# MCU.net
KiCad netlist of a schematic drawn in Altium Designer
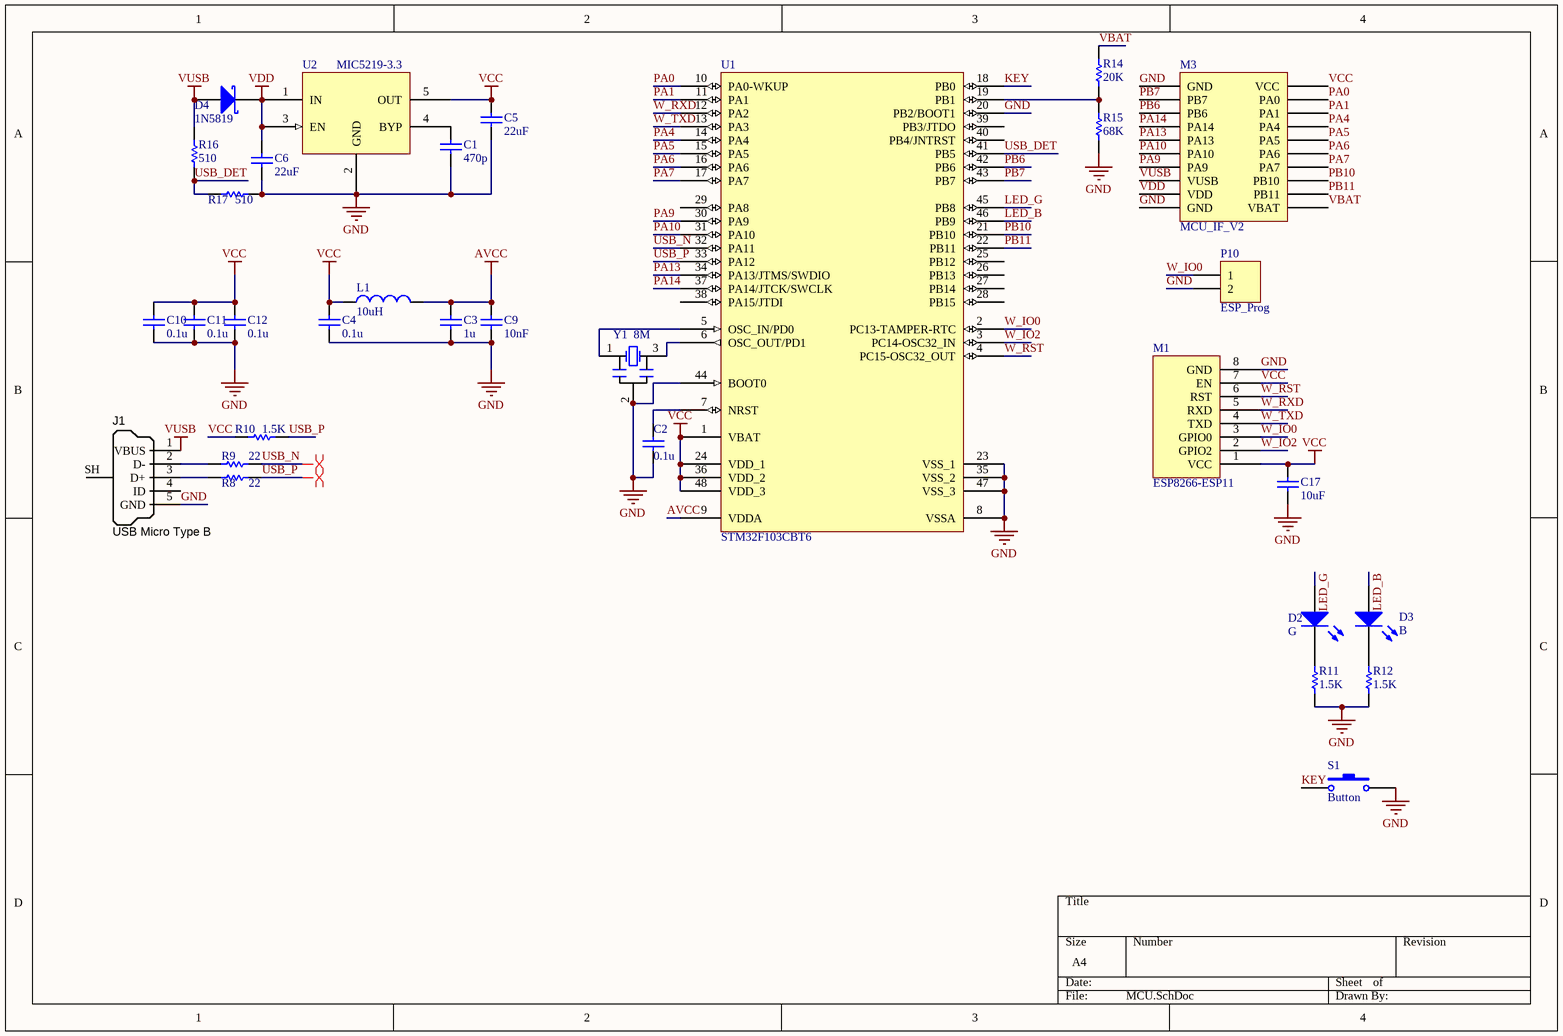
[diagram p0: MCU.SchDoc]

(export (version "E")
  (design (tool "Eeschema 10.0.6"))
  (components
    (comp (ref "C1")
      (value "470p")
      (footprint "C-1608[0603]")
      (description "Capacitor (Semiconductor SIM Model)")
      (fields (field (name "Comment") "Cap Semi") (field (name "PUBLISHER") "Altium Limited"))
      (libsource (lib "Miscellaneous Devices") (part "Cap Semi"))
    )
    (comp (ref "C2")
      (value "0.1u")
      (footprint "C-1608[0603]")
      (description "Capacitor (Semiconductor SIM Model)")
      (fields (field (name "Comment") "Cap Semi") (field (name "PUBLISHER") "Altium Limited"))
      (libsource (lib "Miscellaneous Devices") (part "Cap Semi"))
    )
    (comp (ref "C3")
      (value "1u")
      (footprint "C-1608[0603]")
      (description "Capacitor (Semiconductor SIM Model)")
      (fields (field (name "Comment") "Cap Semi") (field (name "PUBLISHER") "Altium Limited"))
      (libsource (lib "Miscellaneous Devices") (part "Cap Semi"))
    )
    (comp (ref "C4")
      (value "0.1u")
      (footprint "C-1608[0603]")
      (description "Capacitor (Semiconductor SIM Model)")
      (fields (field (name "Comment") "Cap Semi") (field (name "PUBLISHER") "Altium Limited"))
      (libsource (lib "Miscellaneous Devices") (part "Cap Semi"))
    )
    (comp (ref "C5")
      (value "22uF")
      (footprint "C-2012[0805]")
      (description "Capacitor (Semiconductor SIM Model)")
      (fields (field (name "Comment") "Cap Semi") (field (name "PUBLISHER") "Altium Limited"))
      (libsource (lib "Miscellaneous Devices") (part "Cap Semi"))
    )
    (comp (ref "C6")
      (value "22uF")
      (footprint "C-2012[0805]")
      (description "Capacitor (Semiconductor SIM Model)")
      (fields (field (name "Comment") "Cap Semi") (field (name "PUBLISHER") "Altium Limited"))
      (libsource (lib "Miscellaneous Devices") (part "Cap Semi"))
    )
    (comp (ref "C9")
      (value "10nF")
      (footprint "C-1608[0603]")
      (description "Capacitor (Semiconductor SIM Model)")
      (fields (field (name "Comment") "Cap Semi") (field (name "PUBLISHER") "Altium Limited"))
      (libsource (lib "Miscellaneous Devices") (part "Cap Semi"))
    )
    (comp (ref "C10")
      (value "0.1u")
      (footprint "C-1608[0603]")
      (description "Capacitor (Semiconductor SIM Model)")
      (fields (field (name "Comment") "Cap Semi") (field (name "PUBLISHER") "Altium Limited"))
      (libsource (lib "Miscellaneous Devices") (part "Cap Semi"))
    )
    (comp (ref "C11")
      (value "0.1u")
      (footprint "C-1608[0603]")
      (description "Capacitor (Semiconductor SIM Model)")
      (fields (field (name "Comment") "Cap Semi") (field (name "PUBLISHER") "Altium Limited"))
      (libsource (lib "Miscellaneous Devices") (part "Cap Semi"))
    )
    (comp (ref "C12")
      (value "0.1u")
      (footprint "C-1608[0603]")
      (description "Capacitor (Semiconductor SIM Model)")
      (fields (field (name "Comment") "Cap Semi") (field (name "PUBLISHER") "Altium Limited"))
      (libsource (lib "Miscellaneous Devices") (part "Cap Semi"))
    )
    (comp (ref "C17")
      (value "10uF")
      (footprint "C-1608[0603]")
      (description "Capacitor (Semiconductor SIM Model)")
      (fields (field (name "Comment") "Cap Semi") (field (name "PUBLISHER") "Altium Limited"))
      (libsource (lib "Miscellaneous Devices") (part "Cap Semi"))
    )
    (comp (ref "D2")
      (value "G")
      (footprint "LED-1608[0603]-G")
      (description "Green LED")
      (fields (field (name "PUBLISHER") "Altium Limited"))
      (libsource (lib "Miscellaneous Devices") (part "LED2"))
    )
    (comp (ref "D3")
      (value "B")
      (footprint "LED-1608[0603]-B")
      (description "Blue LED")
      (fields (field (name "PUBLISHER") "Altium Limited"))
      (libsource (lib "Miscellaneous Devices") (part "LED2"))
    )
    (comp (ref "D4")
      (value "1N5819")
      (footprint "PcbLib1:SOD123")
      (description "Schottky Diode")
      (fields (field (name "PUBLISHER") "Altium Limited"))
      (libsource (lib "Miscellaneous Devices") (part "D Schottky"))
    )
    (comp (ref "J1")
      (value "USB Micro Type B")
      (footprint "MICRO USB 3D")
      (description "Connector SMD USB Micro Type B middle mount")
      (libsource (lib "Schlib1") (part "USB_Micro_TypeB"))
    )
    (comp (ref "L1")
      (value "10uH")
      (footprint "L-1608[0603]")
      (description "Inductor")
      (fields (field (name "PUBLISHER") "Altium Limited"))
      (libsource (lib "Miscellaneous Devices") (part "Inductor"))
    )
    (comp (ref "M1")
      (value "ESP8266-ESP11")
      (footprint "ESP8266-ESP11")
      (libsource (lib "WiFiMod") (part "ESP8266-ESP11"))
    )
    (comp (ref "M3")
      (value "MCU_IF_V2")
      (footprint "MCU_IF_V2")
      (libsource (lib "MCU_IF") (part "MCU_IF_V1"))
    )
    (comp (ref "P10")
      (value "ESP_Prog")
      (footprint "EDGE_1")
      (description "Header, 2-Pin")
      (fields (field (name "PUBLISHER") "Altium Limited"))
      (libsource (lib "Miscellaneous Connectors") (part "Header 2"))
    )
    (comp (ref "R8")
      (value "22")
      (footprint "R-1608[0603]")
      (description "Semiconductor Resistor")
      (fields (field (name "Comment") "Res Semi") (field (name "PUBLISHER") "Altium Limited"))
      (libsource (lib "Miscellaneous Devices") (part "Res Semi"))
    )
    (comp (ref "R9")
      (value "22")
      (footprint "R-1608[0603]")
      (description "Semiconductor Resistor")
      (fields (field (name "Comment") "Res Semi") (field (name "PUBLISHER") "Altium Limited"))
      (libsource (lib "Miscellaneous Devices") (part "Res Semi"))
    )
    (comp (ref "R10")
      (value "1.5K")
      (footprint "R-1608[0603]")
      (description "Semiconductor Resistor")
      (fields (field (name "Comment") "Res Semi") (field (name "PUBLISHER") "Altium Limited"))
      (libsource (lib "Miscellaneous Devices") (part "Res Semi"))
    )
    (comp (ref "R11")
      (value "1.5K")
      (footprint "R-1608[0603]")
      (description "Semiconductor Resistor")
      (fields (field (name "Comment") "Res Semi") (field (name "PUBLISHER") "Altium Limited"))
      (libsource (lib "Miscellaneous Devices") (part "Res Semi"))
    )
    (comp (ref "R12")
      (value "1.5K")
      (footprint "R-1608[0603]")
      (description "Semiconductor Resistor")
      (fields (field (name "Comment") "Res Semi") (field (name "PUBLISHER") "Altium Limited"))
      (libsource (lib "Miscellaneous Devices") (part "Res Semi"))
    )
    (comp (ref "R14")
      (value "20K")
      (footprint "R-1608[0603]")
      (description "Semiconductor Resistor")
      (fields (field (name "Comment") "Res Semi") (field (name "PUBLISHER") "Altium Limited"))
      (libsource (lib "Miscellaneous Devices") (part "Res Semi"))
    )
    (comp (ref "R15")
      (value "68K")
      (footprint "R-1608[0603]")
      (description "Semiconductor Resistor")
      (fields (field (name "Comment") "Res Semi") (field (name "PUBLISHER") "Altium Limited"))
      (libsource (lib "Miscellaneous Devices") (part "Res Semi"))
    )
    (comp (ref "R16")
      (value "510")
      (footprint "R-1608[0603]")
      (description "Semiconductor Resistor")
      (fields (field (name "Comment") "Res Semi") (field (name "PUBLISHER") "Altium Limited"))
      (libsource (lib "Miscellaneous Devices") (part "Res Semi"))
    )
    (comp (ref "R17")
      (value "510")
      (footprint "R-1608[0603]")
      (description "Semiconductor Resistor")
      (fields (field (name "Comment") "Res Semi") (field (name "PUBLISHER") "Altium Limited"))
      (libsource (lib "Miscellaneous Devices") (part "Res Semi"))
    )
    (comp (ref "S1")
      (value "Button")
      (footprint "SW-2pin-SMD")
      (description "Switch")
      (fields (field (name "PUBLISHER") "Altium Limited"))
      (libsource (lib "Miscellaneous Devices") (part "SW-PB"))
    )
    (comp (ref "U1")
      (value "STM32F103CBT6")
      (footprint "LQFP48_N")
      (description "STM32 ARM-based 32-bit MCU with 128 Kbytes Flash, 48-pin LQFP, Industrial Temperature")
      (fields (field (name "PUBLISHER") "Altium Limited"))
      (libsource (lib "ST Microcontroller 32-Bit STM32") (part "STM32F103CBT6"))
    )
    (comp (ref "U2")
      (value "MIC5219-3.3")
      (footprint "SOT23-5")
      (description "500mA-Peak Output LDO Regulator")
      (libsource (lib "Schlib1") (part "MIC5219"))
    )
    (comp (ref "Y1")
      (value "8M")
      (footprint "Crystal_C")
      (description "Crystal Oscillator")
      (fields (field (name "PUBLISHER") "Altium Limited"))
      (libsource (lib "Schlib1") (part "XTAL_C"))
    )
  )
  (nets
    (net (code "1") (name "/KEY") (class "Default")
      (node (ref "S1") (pin "1") (pinfunction "1_1") (pintype "passive"))
      (node (ref "U1") (pin "18") (pinfunction "PB0_18") (pintype "bidirectional"))
    )
    (net (code "2") (name "/LED_B") (class "Default")
      (node (ref "D3") (pin "1") (pinfunction "A_1") (pintype "passive"))
      (node (ref "U1") (pin "46") (pinfunction "PB9_46") (pintype "bidirectional"))
    )
    (net (code "3") (name "/LED_G") (class "Default")
      (node (ref "D2") (pin "1") (pinfunction "A_1") (pintype "passive"))
      (node (ref "U1") (pin "45") (pinfunction "PB8_45") (pintype "bidirectional"))
    )
    (net (code "4") (name "/PA0") (class "Default")
      (node (ref "M3") (pin "19") (pinfunction "PA0_19") (pintype "passive"))
      (node (ref "U1") (pin "10") (pinfunction "PA0-WKUP_10") (pintype "bidirectional"))
    )
    (net (code "5") (name "/PA1") (class "Default")
      (node (ref "M3") (pin "18") (pinfunction "PA1_18") (pintype "passive"))
      (node (ref "U1") (pin "11") (pinfunction "PA1_11") (pintype "bidirectional"))
    )
    (net (code "6") (name "/PA4") (class "Default")
      (node (ref "M3") (pin "17") (pinfunction "PA4_17") (pintype "passive"))
      (node (ref "U1") (pin "14") (pinfunction "PA4_14") (pintype "bidirectional"))
    )
    (net (code "7") (name "/PA5") (class "Default")
      (node (ref "M3") (pin "16") (pinfunction "PA5_16") (pintype "passive"))
      (node (ref "U1") (pin "15") (pinfunction "PA5_15") (pintype "bidirectional"))
    )
    (net (code "8") (name "/PA6") (class "Default")
      (node (ref "M3") (pin "15") (pinfunction "PA6_15") (pintype "passive"))
      (node (ref "U1") (pin "16") (pinfunction "PA6_16") (pintype "bidirectional"))
    )
    (net (code "9") (name "/PA7") (class "Default")
      (node (ref "M3") (pin "14") (pinfunction "PA7_14") (pintype "passive"))
      (node (ref "U1") (pin "17") (pinfunction "PA7_17") (pintype "bidirectional"))
    )
    (net (code "10") (name "/PA9") (class "Default")
      (node (ref "M3") (pin "7") (pinfunction "PA9_7") (pintype "passive"))
      (node (ref "U1") (pin "30") (pinfunction "PA9_30") (pintype "bidirectional"))
    )
    (net (code "11") (name "/PA10") (class "Default")
      (node (ref "M3") (pin "6") (pinfunction "PA10_6") (pintype "passive"))
      (node (ref "U1") (pin "31") (pinfunction "PA10_31") (pintype "bidirectional"))
    )
    (net (code "12") (name "/PA13") (class "Default")
      (node (ref "M3") (pin "5") (pinfunction "PA13_5") (pintype "passive"))
      (node (ref "U1") (pin "34") (pinfunction "PA13/JTMS/SWDIO_34") (pintype "bidirectional"))
    )
    (net (code "13") (name "/PA14") (class "Default")
      (node (ref "M3") (pin "4") (pinfunction "PA14_4") (pintype "passive"))
      (node (ref "U1") (pin "37") (pinfunction "PA14/JTCK/SWCLK_37") (pintype "bidirectional"))
    )
    (net (code "14") (name "/PB6") (class "Default")
      (node (ref "M3") (pin "3") (pinfunction "PB6_3") (pintype "passive"))
      (node (ref "U1") (pin "42") (pinfunction "PB6_42") (pintype "bidirectional"))
    )
    (net (code "15") (name "/PB7") (class "Default")
      (node (ref "M3") (pin "2") (pinfunction "PB7_2") (pintype "passive"))
      (node (ref "U1") (pin "43") (pinfunction "PB7_43") (pintype "bidirectional"))
    )
    (net (code "16") (name "/PB10") (class "Default")
      (node (ref "M3") (pin "13") (pinfunction "PB10_13") (pintype "passive"))
      (node (ref "U1") (pin "21") (pinfunction "PB10_21") (pintype "bidirectional"))
    )
    (net (code "17") (name "/PB11") (class "Default")
      (node (ref "M3") (pin "12") (pinfunction "PB11_12") (pintype "passive"))
      (node (ref "U1") (pin "22") (pinfunction "PB11_22") (pintype "bidirectional"))
    )
    (net (code "18") (name "/USB_DET") (class "Default")
      (node (ref "R16") (pin "1") (pinfunction "1_1") (pintype "passive"))
      (node (ref "R17") (pin "2") (pinfunction "2_2") (pintype "passive"))
      (node (ref "U1") (pin "41") (pinfunction "PB5_41") (pintype "bidirectional"))
    )
    (net (code "19") (name "/USB_N") (class "Default")
      (node (ref "R9") (pin "2") (pinfunction "2_2") (pintype "passive"))
      (node (ref "U1") (pin "32") (pinfunction "PA11_32") (pintype "bidirectional"))
    )
    (net (code "20") (name "/USB_P") (class "Default")
      (node (ref "R10") (pin "1") (pinfunction "1_1") (pintype "passive"))
      (node (ref "R8") (pin "2") (pinfunction "2_2") (pintype "passive"))
      (node (ref "U1") (pin "33") (pinfunction "PA12_33") (pintype "bidirectional"))
    )
    (net (code "21") (name "/VBAT") (class "Default")
      (node (ref "M3") (pin "11") (pinfunction "VBAT_11") (pintype "passive"))
      (node (ref "R14") (pin "2") (pinfunction "2_2") (pintype "passive"))
    )
    (net (code "22") (name "/W_IO0") (class "Default")
      (node (ref "M1") (pin "3") (pinfunction "GPIO0_3") (pintype "passive"))
      (node (ref "P10") (pin "1") (pinfunction "1_1") (pintype "passive"))
      (node (ref "U1") (pin "2") (pinfunction "PC13-TAMPER-RTC_2") (pintype "bidirectional"))
    )
    (net (code "23") (name "/W_IO2") (class "Default")
      (node (ref "M1") (pin "2") (pinfunction "GPIO2_2") (pintype "passive"))
      (node (ref "U1") (pin "3") (pinfunction "PC14-OSC32_IN_3") (pintype "bidirectional"))
    )
    (net (code "24") (name "/W_RST") (class "Default")
      (node (ref "M1") (pin "6") (pinfunction "RST_6") (pintype "passive"))
      (node (ref "U1") (pin "4") (pinfunction "PC15-OSC32_OUT_4") (pintype "bidirectional"))
    )
    (net (code "25") (name "/W_RXD") (class "Default")
      (node (ref "M1") (pin "5") (pinfunction "RXD_5") (pintype "passive"))
      (node (ref "U1") (pin "12") (pinfunction "PA2_12") (pintype "bidirectional"))
    )
    (net (code "26") (name "/W_TXD") (class "Default")
      (node (ref "M1") (pin "4") (pinfunction "TXD_4") (pintype "passive"))
      (node (ref "U1") (pin "13") (pinfunction "PA3_13") (pintype "bidirectional"))
    )
    (net (code "27") (name "AVCC") (class "Default")
      (node (ref "C3") (pin "2") (pinfunction "2_2") (pintype "passive"))
      (node (ref "C9") (pin "2") (pinfunction "2_2") (pintype "passive"))
      (node (ref "L1") (pin "2") (pinfunction "2_2") (pintype "passive"))
      (node (ref "U1") (pin "9") (pinfunction "VDDA_9") (pintype "power_in"))
    )
    (net (code "28") (name "GND") (class "Default")
      (node (ref "C1") (pin "2") (pinfunction "2_2") (pintype "passive"))
      (node (ref "C10") (pin "1") (pinfunction "1_1") (pintype "passive"))
      (node (ref "C11") (pin "1") (pinfunction "1_1") (pintype "passive"))
      (node (ref "C12") (pin "1") (pinfunction "1_1") (pintype "passive"))
      (node (ref "C17") (pin "1") (pinfunction "1_1") (pintype "passive"))
      (node (ref "C2") (pin "1") (pinfunction "1_1") (pintype "passive"))
      (node (ref "C3") (pin "1") (pinfunction "1_1") (pintype "passive"))
      (node (ref "C4") (pin "1") (pinfunction "1_1") (pintype "passive"))
      (node (ref "C5") (pin "2") (pinfunction "2_2") (pintype "passive"))
      (node (ref "C6") (pin "2") (pinfunction "2_2") (pintype "passive"))
      (node (ref "C9") (pin "1") (pinfunction "1_1") (pintype "passive"))
      (node (ref "J1") (pin "5") (pinfunction "GND_5") (pintype "passive"))
      (node (ref "M1") (pin "8") (pinfunction "GND_8") (pintype "passive"))
      (node (ref "M3") (pin "1") (pinfunction "GND_1") (pintype "passive"))
      (node (ref "M3") (pin "10") (pinfunction "GND_10") (pintype "passive"))
      (node (ref "P10") (pin "2") (pinfunction "2_2") (pintype "passive"))
      (node (ref "R11") (pin "2") (pinfunction "2_2") (pintype "passive"))
      (node (ref "R12") (pin "2") (pinfunction "2_2") (pintype "passive"))
      (node (ref "R15") (pin "2") (pinfunction "2_2") (pintype "passive"))
      (node (ref "R17") (pin "1") (pinfunction "1_1") (pintype "passive"))
      (node (ref "S1") (pin "2") (pinfunction "2_2") (pintype "passive"))
      (node (ref "U1") (pin "20") (pinfunction "PB2/BOOT1_20") (pintype "bidirectional"))
      (node (ref "U1") (pin "23") (pinfunction "VSS_1_23") (pintype "power_in"))
      (node (ref "U1") (pin "35") (pinfunction "VSS_2_35") (pintype "power_in"))
      (node (ref "U1") (pin "44") (pinfunction "BOOT0_44") (pintype "input"))
      (node (ref "U1") (pin "47") (pinfunction "VSS_3_47") (pintype "power_in"))
      (node (ref "U1") (pin "8") (pinfunction "VSSA_8") (pintype "power_in"))
      (node (ref "U2") (pin "2") (pinfunction "GND_2") (pintype "passive"))
      (node (ref "Y1") (pin "2") (pinfunction "GND_2") (pintype "passive"))
    )
    (net (code "29") (name "Net-(D2-K)") (class "Default")
      (node (ref "D2") (pin "2") (pinfunction "K_2") (pintype "passive"))
      (node (ref "R11") (pin "1") (pinfunction "1_1") (pintype "passive"))
    )
    (net (code "30") (name "Net-(D3-K)") (class "Default")
      (node (ref "D3") (pin "2") (pinfunction "K_2") (pintype "passive"))
      (node (ref "R12") (pin "1") (pinfunction "1_1") (pintype "passive"))
    )
    (net (code "31") (name "Net-(J1-D+)") (class "Default")
      (node (ref "J1") (pin "3") (pinfunction "D+_3") (pintype "passive"))
      (node (ref "R8") (pin "1") (pinfunction "1_1") (pintype "passive"))
    )
    (net (code "32") (name "Net-(J1-D-)") (class "Default")
      (node (ref "J1") (pin "2") (pinfunction "D-_2") (pintype "passive"))
      (node (ref "R9") (pin "1") (pinfunction "1_1") (pintype "passive"))
    )
    (net (code "33") (name "Net-(U1-NRST)") (class "Default")
      (node (ref "C2") (pin "2") (pinfunction "2_2") (pintype "passive"))
      (node (ref "U1") (pin "7") (pinfunction "NRST_7") (pintype "bidirectional"))
    )
    (net (code "34") (name "Net-(U1-OSC_IN{slash}PD0)") (class "Default")
      (node (ref "U1") (pin "5") (pinfunction "OSC_IN/PD0_5") (pintype "input"))
      (node (ref "Y1") (pin "1") (pinfunction "OSC1_1") (pintype "passive"))
    )
    (net (code "35") (name "Net-(U1-OSC_OUT{slash}PD1)") (class "Default")
      (node (ref "U1") (pin "6") (pinfunction "OSC_OUT/PD1_6") (pintype "output"))
      (node (ref "Y1") (pin "3") (pinfunction "OSC2_3") (pintype "passive"))
    )
    (net (code "36") (name "Net-(U1-PB1)") (class "Default")
      (node (ref "R14") (pin "1") (pinfunction "1_1") (pintype "passive"))
      (node (ref "R15") (pin "1") (pinfunction "1_1") (pintype "passive"))
      (node (ref "U1") (pin "19") (pinfunction "PB1_19") (pintype "bidirectional"))
    )
    (net (code "37") (name "Net-(U2-BYP)") (class "Default")
      (node (ref "C1") (pin "1") (pinfunction "1_1") (pintype "passive"))
      (node (ref "U2") (pin "4") (pinfunction "BYP_4") (pintype "passive"))
    )
    (net (code "38") (name "VCC") (class "Default")
      (node (ref "C10") (pin "2") (pinfunction "2_2") (pintype "passive"))
      (node (ref "C11") (pin "2") (pinfunction "2_2") (pintype "passive"))
      (node (ref "C12") (pin "2") (pinfunction "2_2") (pintype "passive"))
      (node (ref "C17") (pin "2") (pinfunction "2_2") (pintype "passive"))
      (node (ref "C4") (pin "2") (pinfunction "2_2") (pintype "passive"))
      (node (ref "C5") (pin "1") (pinfunction "1_1") (pintype "passive"))
      (node (ref "L1") (pin "1") (pinfunction "1_1") (pintype "passive"))
      (node (ref "M1") (pin "1") (pinfunction "VCC_1") (pintype "power_in"))
      (node (ref "M1") (pin "7") (pinfunction "EN_7") (pintype "passive"))
      (node (ref "M3") (pin "20") (pinfunction "VCC_20") (pintype "passive"))
      (node (ref "R10") (pin "2") (pinfunction "2_2") (pintype "passive"))
      (node (ref "U1") (pin "1") (pinfunction "VBAT_1") (pintype "power_in"))
      (node (ref "U1") (pin "24") (pinfunction "VDD_1_24") (pintype "power_in"))
      (node (ref "U1") (pin "36") (pinfunction "VDD_2_36") (pintype "power_in"))
      (node (ref "U1") (pin "48") (pinfunction "VDD_3_48") (pintype "power_in"))
      (node (ref "U2") (pin "5") (pinfunction "OUT_5") (pintype "passive"))
    )
    (net (code "39") (name "VDD") (class "Default")
      (node (ref "C6") (pin "1") (pinfunction "1_1") (pintype "passive"))
      (node (ref "D4") (pin "2") (pinfunction "K_2") (pintype "passive"))
      (node (ref "M3") (pin "9") (pinfunction "VDD_9") (pintype "passive"))
      (node (ref "U2") (pin "1") (pinfunction "IN_1") (pintype "power_in"))
      (node (ref "U2") (pin "3") (pinfunction "EN_3") (pintype "input"))
    )
    (net (code "40") (name "VUSB") (class "Default")
      (node (ref "D4") (pin "1") (pinfunction "A_1") (pintype "passive"))
      (node (ref "J1") (pin "1") (pinfunction "VBUS_1") (pintype "passive"))
      (node (ref "M3") (pin "8") (pinfunction "VUSB_8") (pintype "passive"))
      (node (ref "R16") (pin "2") (pinfunction "2_2") (pintype "passive"))
    )
    (net (code "41") (name "unconnected-(J1-ID-Pad4)") (class "Default")
      (node (ref "J1") (pin "4") (pinfunction "ID_4") (pintype "passive"))
    )
    (net (code "42") (name "unconnected-(J1-Shell-PadSH)") (class "Default")
      (node (ref "J1") (pin "SH") (pinfunction "Shell_SH") (pintype "passive"))
    )
    (net (code "43") (name "unconnected-(U1-PA8-Pad29)") (class "Default")
      (node (ref "U1") (pin "29") (pinfunction "PA8_29") (pintype "bidirectional"))
    )
    (net (code "44") (name "unconnected-(U1-PA15{slash}JTDI-Pad38)") (class "Default")
      (node (ref "U1") (pin "38") (pinfunction "PA15/JTDI_38") (pintype "bidirectional"))
    )
    (net (code "45") (name "unconnected-(U1-PB3{slash}JTDO-Pad39)") (class "Default")
      (node (ref "U1") (pin "39") (pinfunction "PB3/JTDO_39") (pintype "bidirectional"))
    )
    (net (code "46") (name "unconnected-(U1-PB4{slash}JNTRST-Pad40)") (class "Default")
      (node (ref "U1") (pin "40") (pinfunction "PB4/JNTRST_40") (pintype "bidirectional"))
    )
    (net (code "47") (name "unconnected-(U1-PB12-Pad25)") (class "Default")
      (node (ref "U1") (pin "25") (pinfunction "PB12_25") (pintype "bidirectional"))
    )
    (net (code "48") (name "unconnected-(U1-PB13-Pad26)") (class "Default")
      (node (ref "U1") (pin "26") (pinfunction "PB13_26") (pintype "bidirectional"))
    )
    (net (code "49") (name "unconnected-(U1-PB14-Pad27)") (class "Default")
      (node (ref "U1") (pin "27") (pinfunction "PB14_27") (pintype "bidirectional"))
    )
    (net (code "50") (name "unconnected-(U1-PB15-Pad28)") (class "Default")
      (node (ref "U1") (pin "28") (pinfunction "PB15_28") (pintype "bidirectional"))
    )
  )
)
